# STorM32_NT_splitter_v001.net
KiCad netlist of a schematic drawn in EAGLE
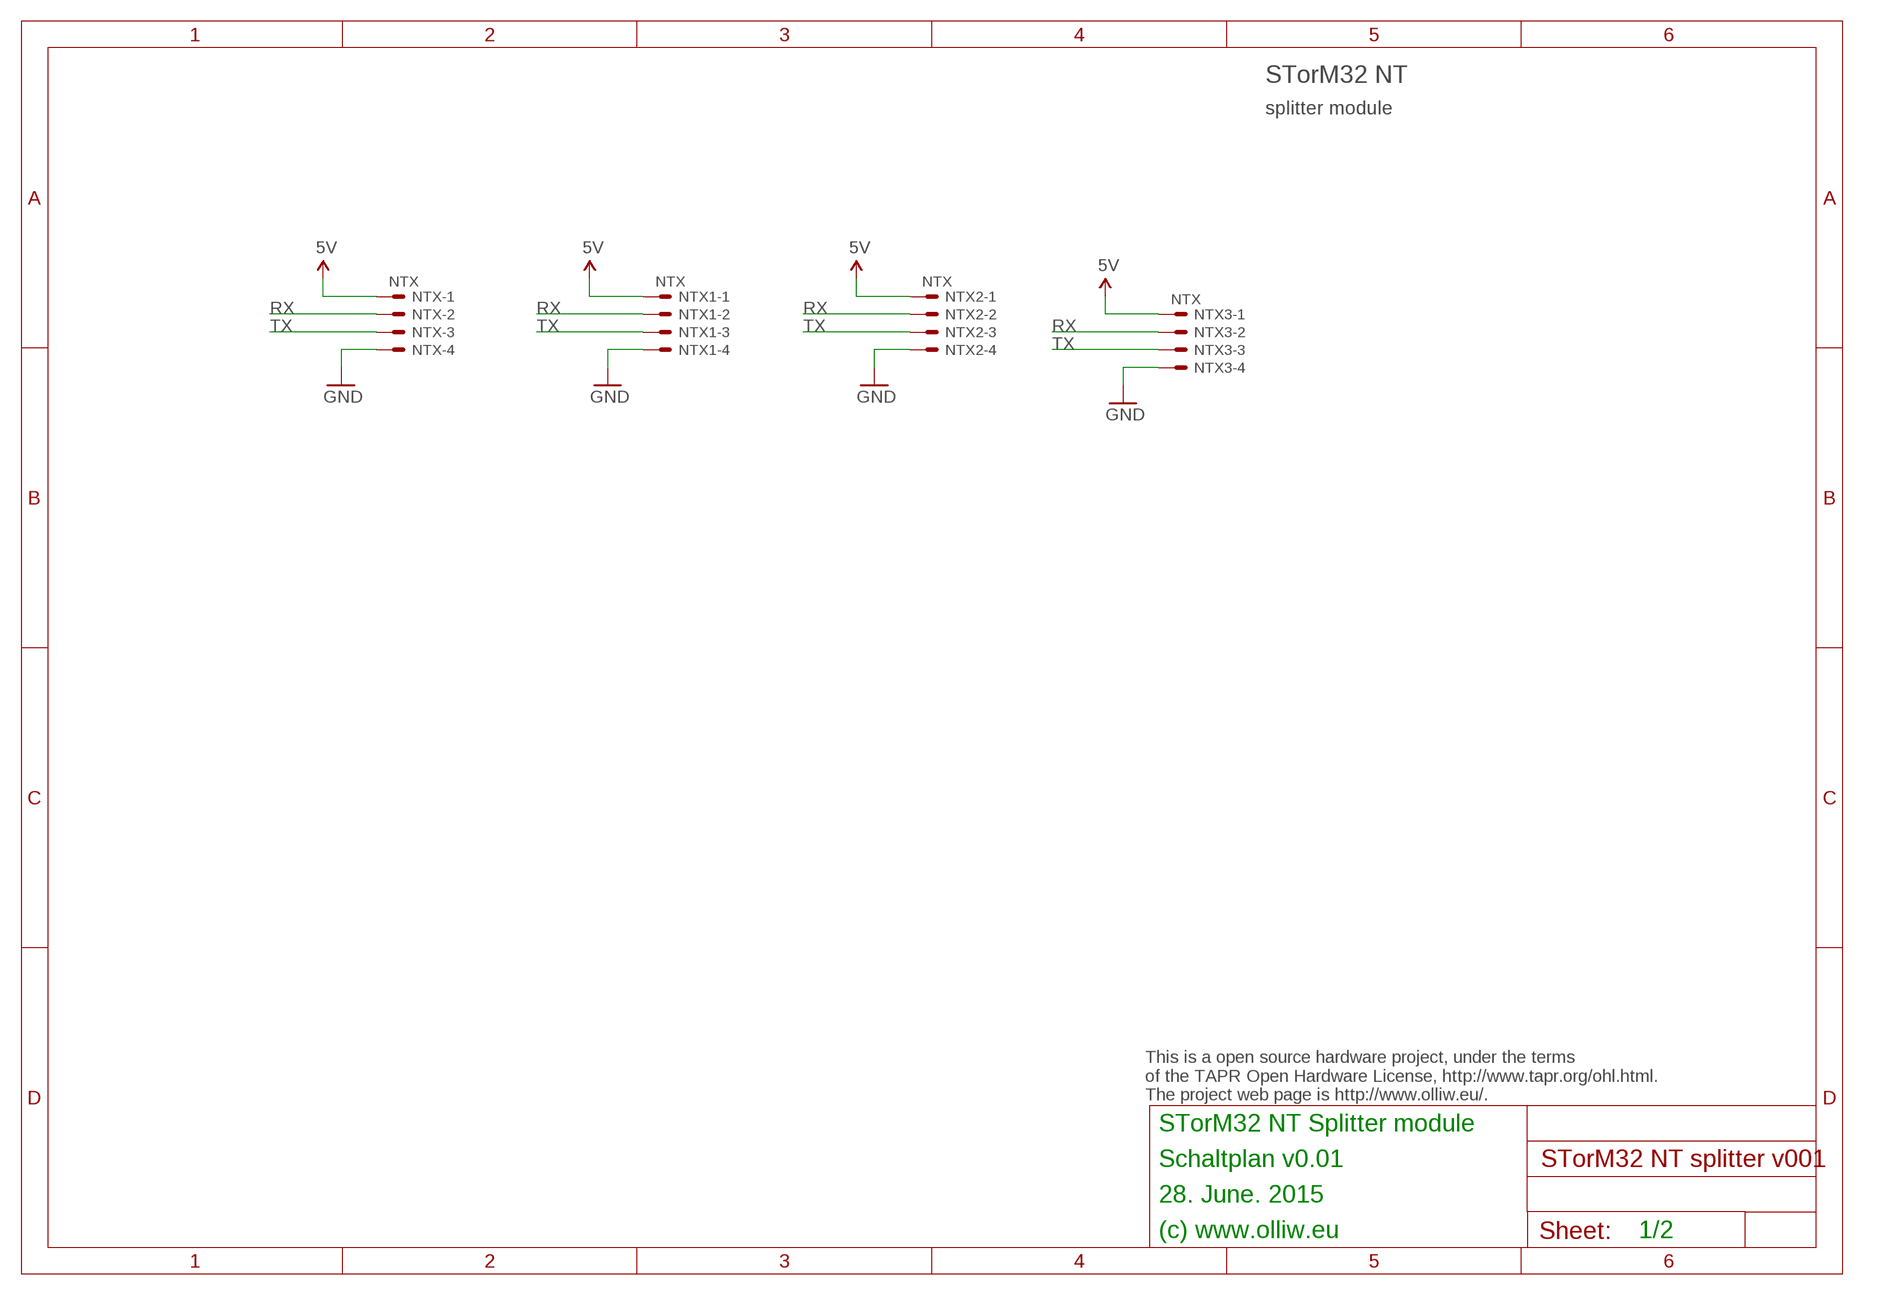
[diagram p0: schematic, sheet 1]

(export (version "E")
  (design (tool "Eeschema 10.0.6"))
  (components
    (comp (ref "NTX")
      (value "NTX")
      (footprint "eagle-import:SM04B-SRSS-TB")
      (libsource (lib "eagle-import") (part "?M04B-SRSS-TBS"))
    )
    (comp (ref "NTX1")
      (value "NTX")
      (footprint "eagle-import:SM04B-SRSS-TB")
      (libsource (lib "eagle-import") (part "?M04B-SRSS-TBS"))
    )
    (comp (ref "NTX2")
      (value "NTX")
      (footprint "eagle-import:SM04B-SRSS-TB")
      (libsource (lib "eagle-import") (part "?M04B-SRSS-TBS"))
    )
    (comp (ref "NTX3")
      (value "NTX")
      (footprint "eagle-import:SM04B-SRSS-TB")
      (libsource (lib "eagle-import") (part "?M04B-SRSS-TBS"))
    )
  )
  (nets
    (net (code "1") (name "/RX") (class "Default")
      (node (ref "NTX") (pin "2") (pinfunction "S_2") (pintype "passive"))
      (node (ref "NTX1") (pin "2") (pinfunction "S_2") (pintype "passive"))
      (node (ref "NTX2") (pin "2") (pinfunction "S_2") (pintype "passive"))
      (node (ref "NTX3") (pin "2") (pinfunction "S_2") (pintype "passive"))
    )
    (net (code "2") (name "/TX") (class "Default")
      (node (ref "NTX") (pin "3") (pinfunction "S_3") (pintype "passive"))
      (node (ref "NTX1") (pin "3") (pinfunction "S_3") (pintype "passive"))
      (node (ref "NTX2") (pin "3") (pinfunction "S_3") (pintype "passive"))
      (node (ref "NTX3") (pin "3") (pinfunction "S_3") (pintype "passive"))
    )
    (net (code "3") (name "5V") (class "Default")
      (node (ref "NTX") (pin "1") (pinfunction "S_1") (pintype "passive"))
      (node (ref "NTX1") (pin "1") (pinfunction "S_1") (pintype "passive"))
      (node (ref "NTX2") (pin "1") (pinfunction "S_1") (pintype "passive"))
      (node (ref "NTX3") (pin "1") (pinfunction "S_1") (pintype "passive"))
    )
    (net (code "4") (name "GND") (class "Default")
      (node (ref "NTX") (pin "4") (pinfunction "S_4") (pintype "passive"))
      (node (ref "NTX1") (pin "4") (pinfunction "S_4") (pintype "passive"))
      (node (ref "NTX2") (pin "4") (pinfunction "S_4") (pintype "passive"))
      (node (ref "NTX3") (pin "4") (pinfunction "S_4") (pintype "passive"))
    )
  )
)
